# LoRa_stm32.net
KiCad netlist of a schematic drawn in Altium Designer
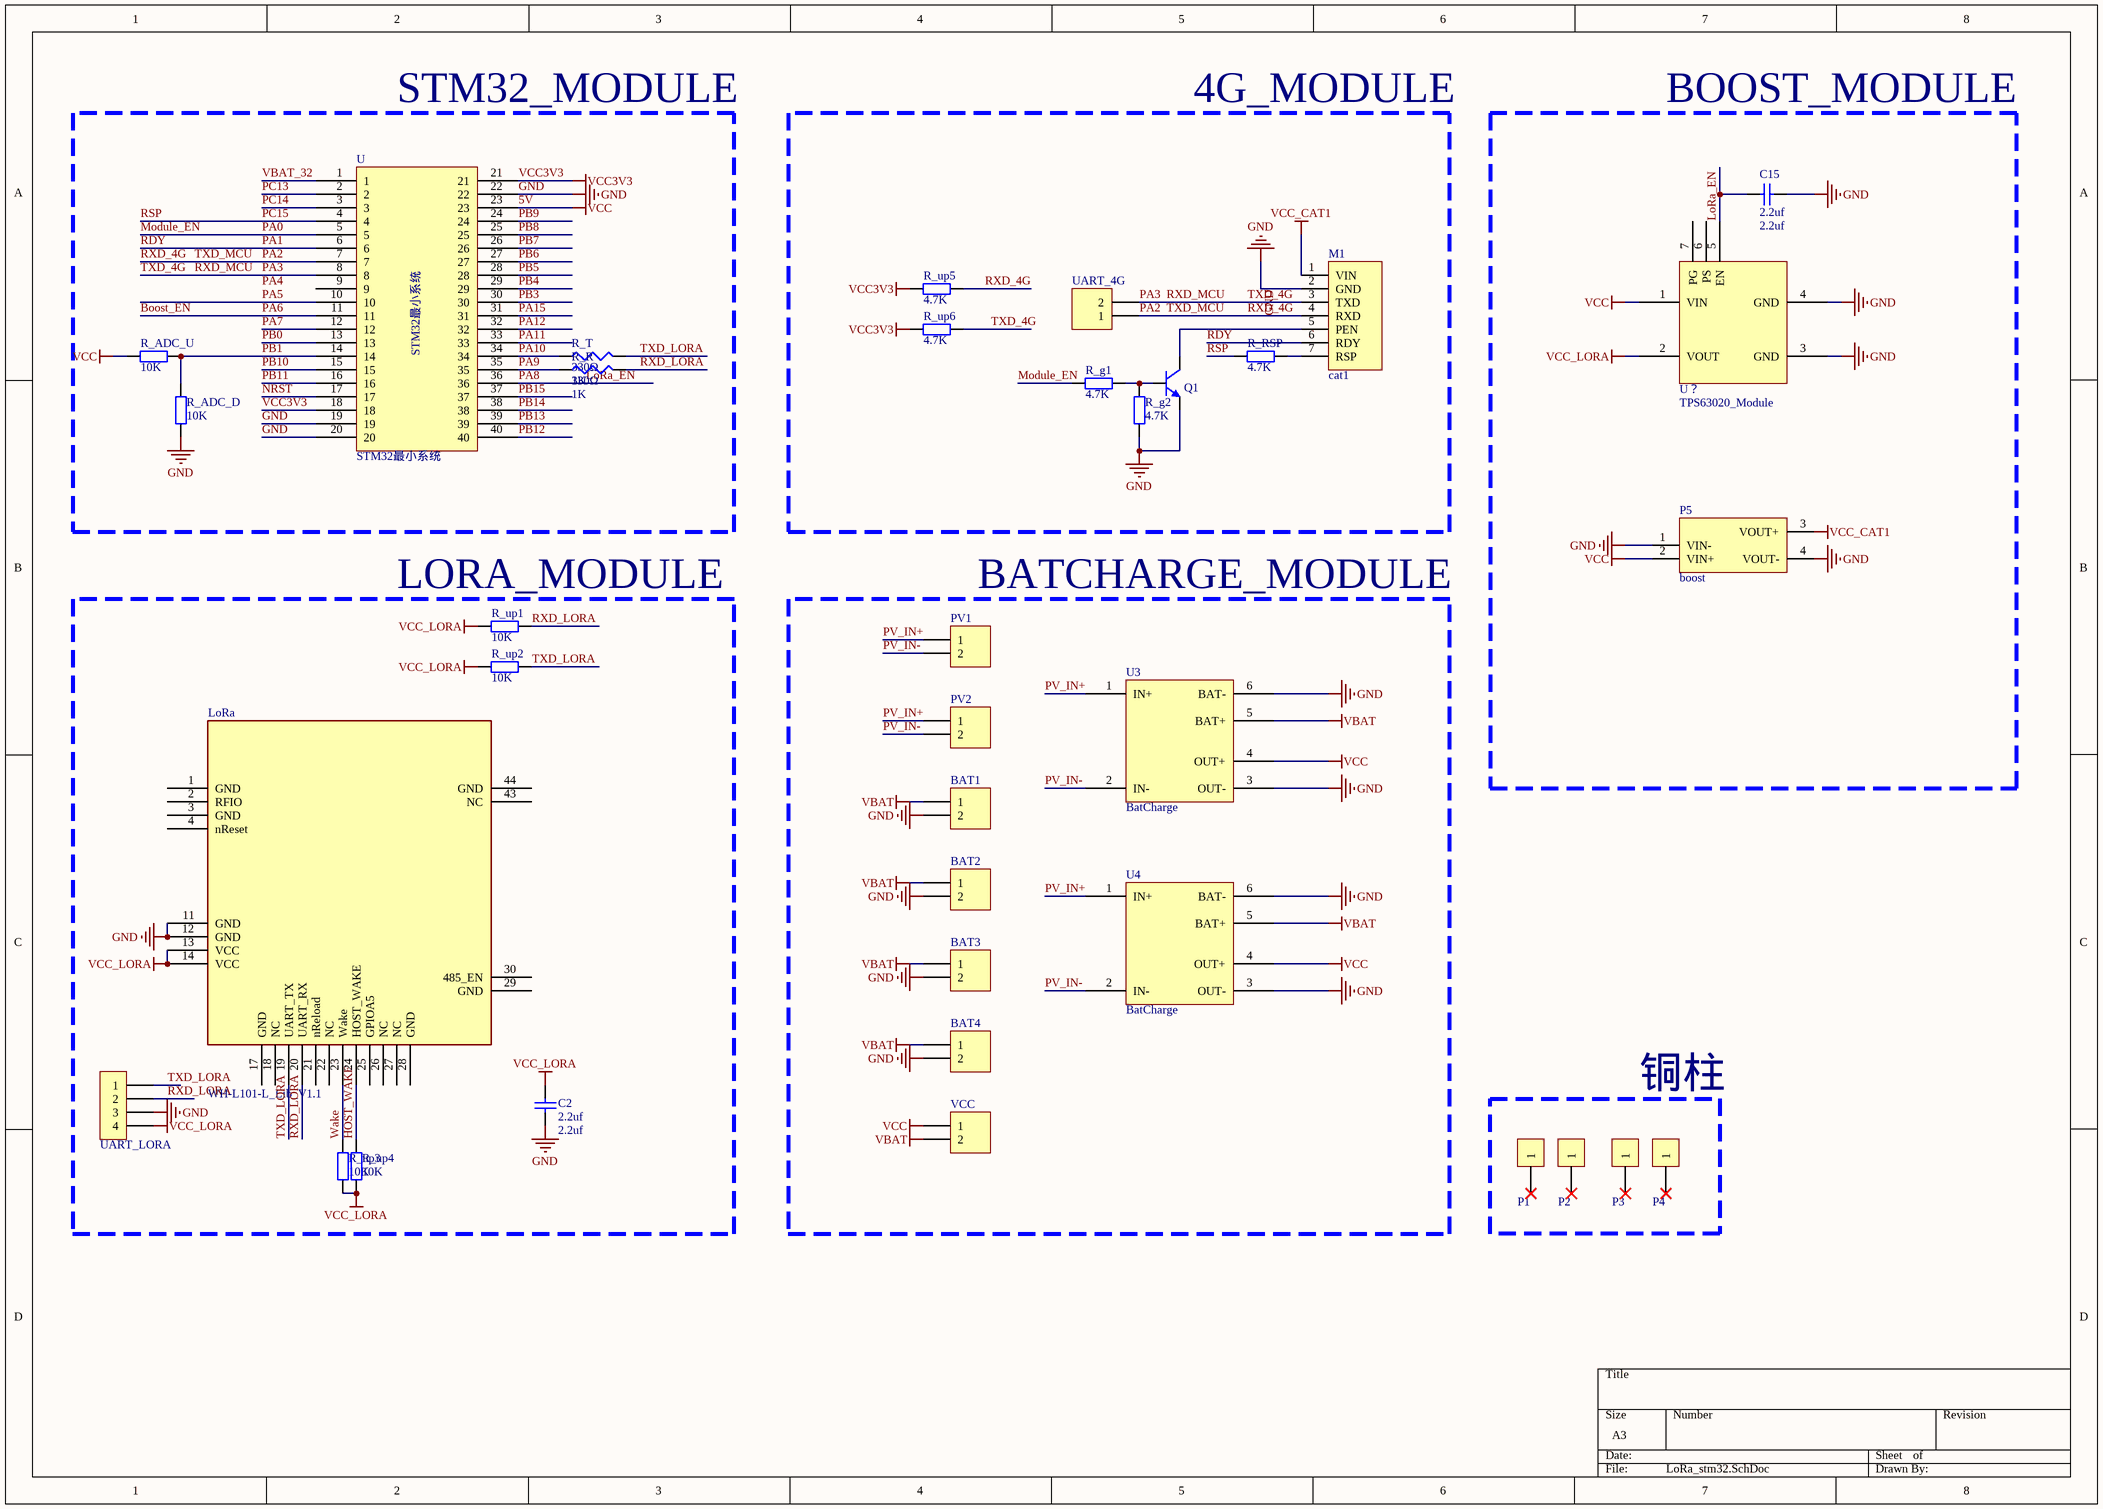
[diagram p0: LoRa_stm32.SchDoc]

(export (version "E")
  (design (tool "Eeschema 10.0.6"))
  (components
    (comp (ref "BAT1")
      (value "UART_4G")
      (footprint "XH-2P")
      (description "Header, 2-Pin")
      (fields (field (name "PUBLISHER") "Altium Limited"))
      (libsource (lib "Miscellaneous Connectors") (part "Header 2"))
    )
    (comp (ref "BAT2")
      (value "UART_4G")
      (footprint "XH-2P")
      (description "Header, 2-Pin")
      (fields (field (name "PUBLISHER") "Altium Limited"))
      (libsource (lib "Miscellaneous Connectors") (part "Header 2"))
    )
    (comp (ref "BAT3")
      (value "UART_4G")
      (footprint "XH-2P")
      (description "Header, 2-Pin")
      (fields (field (name "PUBLISHER") "Altium Limited"))
      (libsource (lib "Miscellaneous Connectors") (part "Header 2"))
    )
    (comp (ref "BAT4")
      (value "UART_4G")
      (footprint "XH-2P")
      (description "Header, 2-Pin")
      (fields (field (name "PUBLISHER") "Altium Limited"))
      (libsource (lib "Miscellaneous Connectors") (part "Header 2"))
    )
    (comp (ref "C2")
      (value "2.2uf")
      (footprint "Csust_czq6:0603-C")
      (description "Capacitor")
      (fields (field (name "ALTIUM_VALUE") "2.2uf") (field (name "PUBLISHER") "Altium Limited"))
      (libsource (lib "PCB_Project") (part "Cap"))
    )
    (comp (ref "C15")
      (value "2.2uf")
      (footprint "Csust_czq6:0603-C")
      (description "Capacitor")
      (fields (field (name "ALTIUM_VALUE") "2.2uf") (field (name "PUBLISHER") "Altium Limited"))
      (libsource (lib "PCB_Project") (part "Cap"))
    )
    (comp (ref "LoRa")
      (value "WH-L101-L_Lib_V1.1")
      (footprint "SMD-44_18.22X26.65X1.27P")
      (libsource (lib "steven") (part "WH-L101-L_Lib_V1.1"))
    )
    (comp (ref "M1")
      (value "cat1")
      (footprint "MCore724")
      (description "4G透传模块")
      (libsource (lib "steven") (part "MCore_A724UG"))
    )
    (comp (ref "P1") (value "铜柱孔") (footprint "铜柱孔") (libsource (lib "Csust_czq6") (part "铜柱孔")))
    (comp (ref "P2") (value "铜柱孔") (footprint "铜柱孔") (libsource (lib "Csust_czq6") (part "铜柱孔")))
    (comp (ref "P3") (value "铜柱孔") (footprint "铜柱孔") (libsource (lib "Csust_czq6") (part "铜柱孔")))
    (comp (ref "P4") (value "铜柱孔") (footprint "铜柱孔") (libsource (lib "Csust_czq6") (part "铜柱孔")))
    (comp (ref "P5")
      (value "boost")
      (footprint "锂电池升压")
      (description "锂电池升压至5/8/9/12V")
      (libsource (lib "steven") (part "Boost12V"))
    )
    (comp (ref "PV1")
      (value "UART_4G")
      (footprint "XH-2P")
      (description "Header, 2-Pin")
      (fields (field (name "PUBLISHER") "Altium Limited"))
      (libsource (lib "Miscellaneous Connectors") (part "Header 2"))
    )
    (comp (ref "PV2")
      (value "UART_4G")
      (footprint "XH-2P")
      (description "Header, 2-Pin")
      (fields (field (name "PUBLISHER") "Altium Limited"))
      (libsource (lib "Miscellaneous Connectors") (part "Header 2"))
    )
    (comp (ref "Q1") (value "三极管(NPN)") (footprint "TO-92") (libsource (lib "Csust_czq6") (part "三极管(NPN)")))
    (comp (ref "R_ADC_D")
      (value "10K")
      (footprint "Csust_czq6:0603-R")
      (description "贴片电阻")
      (fields (field (name "PUBLISHER") "Altium Limited"))
      (libsource (lib "") (part "Res1_1"))
    )
    (comp (ref "R_ADC_U")
      (value "10K")
      (footprint "Csust_czq6:0603-R")
      (description "贴片电阻")
      (fields (field (name "PUBLISHER") "Altium Limited"))
      (libsource (lib "Fszhang") (part "Res1"))
    )
    (comp (ref "R_g1")
      (value "4.7K")
      (footprint "Csust_czq6:0603-R")
      (description "贴片电阻")
      (fields (field (name "Comment") "10K") (field (name "PUBLISHER") "Altium Limited"))
      (libsource (lib "Fszhang") (part "Res1"))
    )
    (comp (ref "R_g2")
      (value "4.7K")
      (footprint "Csust_czq6:0603-R")
      (description "贴片电阻")
      (fields (field (name "Comment") "10K") (field (name "PUBLISHER") "Altium Limited"))
      (libsource (lib "") (part "Res1_1"))
    )
    (comp (ref "R_R")
      (value "330Ω")
      (footprint "J1-0603")
      (description "Resistor")
      (fields (field (name "ALTIUM_VALUE") "1K") (field (name "PUBLISHER") "Altium Limited"))
      (libsource (lib "Miscellaneous Devices") (part "Res3"))
    )
    (comp (ref "R_RSP")
      (value "4.7K")
      (footprint "Csust_czq6:0603-R")
      (description "贴片电阻")
      (fields (field (name "Comment") "10K") (field (name "PUBLISHER") "Altium Limited"))
      (libsource (lib "Fszhang") (part "Res1"))
    )
    (comp (ref "R_T")
      (value "330Ω")
      (footprint "J1-0603")
      (description "Resistor")
      (fields (field (name "ALTIUM_VALUE") "1K") (field (name "PUBLISHER") "Altium Limited"))
      (libsource (lib "Miscellaneous Devices") (part "Res3"))
    )
    (comp (ref "R_up1")
      (value "10K")
      (footprint "Csust_czq6:0603-R")
      (description "贴片电阻")
      (fields (field (name "PUBLISHER") "Altium Limited"))
      (libsource (lib "Fszhang") (part "Res1"))
    )
    (comp (ref "R_up2")
      (value "10K")
      (footprint "Csust_czq6:0603-R")
      (description "贴片电阻")
      (fields (field (name "PUBLISHER") "Altium Limited"))
      (libsource (lib "Fszhang") (part "Res1"))
    )
    (comp (ref "R_up3")
      (value "10K")
      (footprint "Csust_czq6:0603-R")
      (description "贴片电阻")
      (fields (field (name "PUBLISHER") "Altium Limited"))
      (libsource (lib "") (part "Res1_1"))
    )
    (comp (ref "R_up4")
      (value "10K")
      (footprint "Csust_czq6:0603-R")
      (description "贴片电阻")
      (fields (field (name "PUBLISHER") "Altium Limited"))
      (libsource (lib "") (part "Res1_1"))
    )
    (comp (ref "R_up5")
      (value "4.7K")
      (footprint "Csust_czq6:0603-R")
      (description "贴片电阻")
      (fields (field (name "Comment") "10K") (field (name "PUBLISHER") "Altium Limited"))
      (libsource (lib "Fszhang") (part "Res1"))
    )
    (comp (ref "R_up6")
      (value "4.7K")
      (footprint "Csust_czq6:0603-R")
      (description "贴片电阻")
      (fields (field (name "Comment") "10K") (field (name "PUBLISHER") "Altium Limited"))
      (libsource (lib "Fszhang") (part "Res1"))
    )
    (comp (ref "U") (value "STM32最小系统") (footprint "STM32最小系统") (libsource (lib "steven") (part "STM32最小系统")))
    (comp (ref "U3")
      (value "BatCharge")
      (footprint "Bat_Charge")
      (description "电池充电模块")
      (libsource (lib "steven") (part "BatCharge"))
    )
    (comp (ref "U4")
      (value "BatCharge")
      (footprint "Bat_Charge")
      (description "电池充电模块")
      (libsource (lib "steven") (part "BatCharge"))
    )
    (comp (ref "UART_4G")
      (value "UART_4G")
      (footprint "HDR1X2")
      (description "Header, 2-Pin")
      (fields (field (name "PUBLISHER") "Altium Limited"))
      (libsource (lib "") (part "Header 2_1"))
    )
    (comp (ref "UART_LORA")
      (value "XH接线座-4P")
      (footprint "HDR1X4")
      (libsource (lib "Csust_czq6") (part "XH接线座-4P"))
    )
    (comp (ref "U？")
      (value "TPS63020_Module")
      (footprint "TP63020_MODULE")
      (description "升压模块模块")
      (libsource (lib "steven") (part "TPS63020_Module"))
    )
    (comp (ref "VCC")
      (value "UART_4G")
      (footprint "Header1X2")
      (description "Header, 2-Pin")
      (fields (field (name "PUBLISHER") "Altium Limited"))
      (libsource (lib "Miscellaneous Connectors") (part "Header 2"))
    )
  )
  (nets
    (net (code "1") (name "/Boost_EN") (class "Default")
      (node (ref "U") (pin "11") (pinfunction "11_11") (pintype "passive"))
    )
    (net (code "2") (name "/HOST_WAKE") (class "Default")
      (node (ref "LoRa") (pin "24") (pinfunction "HOST_WAKE_24") (pintype "passive"))
      (node (ref "R_up4") (pin "1") (pinfunction "1_1") (pintype "passive"))
    )
    (net (code "3") (name "/LoRa_EN") (class "Default")
      (node (ref "C15") (pin "1") (pinfunction "1_1") (pintype "passive"))
      (node (ref "U") (pin "36") (pinfunction "36_36") (pintype "passive"))
      (node (ref "U？") (pin "5") (pinfunction "EN_5") (pintype "passive"))
    )
    (net (code "4") (name "/Module_EN") (class "Default")
      (node (ref "R_g1") (pin "2") (pinfunction "2_2") (pintype "passive"))
      (node (ref "U") (pin "5") (pinfunction "5_5") (pintype "passive"))
    )
    (net (code "5") (name "/NRST") (class "Default")
      (node (ref "U") (pin "17") (pinfunction "17_17") (pintype "passive"))
    )
    (net (code "6") (name "/PA1") (class "Default")
      (node (ref "M1") (pin "6") (pinfunction "RDY_6") (pintype "passive"))
      (node (ref "U") (pin "6") (pinfunction "6_6") (pintype "passive"))
    )
    (net (code "7") (name "/PA2") (class "Default")
      (node (ref "M1") (pin "4") (pinfunction "RXD_4") (pintype "passive"))
      (node (ref "R_up5") (pin "1") (pinfunction "1_1") (pintype "passive"))
      (node (ref "U") (pin "7") (pinfunction "7_7") (pintype "passive"))
      (node (ref "UART_4G") (pin "1") (pinfunction "1_1") (pintype "passive"))
    )
    (net (code "8") (name "/PA3") (class "Default")
      (node (ref "M1") (pin "3") (pinfunction "TXD_3") (pintype "passive"))
      (node (ref "R_up6") (pin "1") (pinfunction "1_1") (pintype "passive"))
      (node (ref "U") (pin "8") (pinfunction "8_8") (pintype "passive"))
      (node (ref "UART_4G") (pin "2") (pinfunction "2_2") (pintype "passive"))
    )
    (net (code "10") (name "/PA5") (class "Default")
      (node (ref "U") (pin "10") (pinfunction "10_10") (pintype "passive"))
    )
    (net (code "11") (name "/PA7") (class "Default")
      (node (ref "U") (pin "12") (pinfunction "12_12") (pintype "passive"))
    )
    (net (code "12") (name "/PA9") (class "Default")
      (node (ref "R_R") (pin "1") (pinfunction "1_1") (pintype "passive"))
      (node (ref "U") (pin "35") (pinfunction "35_35") (pintype "passive"))
    )
    (net (code "13") (name "/PA10") (class "Default")
      (node (ref "R_T") (pin "1") (pinfunction "1_1") (pintype "passive"))
      (node (ref "U") (pin "34") (pinfunction "34_34") (pintype "passive"))
    )
    (net (code "14") (name "/PA11") (class "Default")
      (node (ref "U") (pin "33") (pinfunction "33_33") (pintype "passive"))
    )
    (net (code "15") (name "/PA12") (class "Default")
      (node (ref "U") (pin "32") (pinfunction "32_32") (pintype "passive"))
    )
    (net (code "16") (name "/PA15") (class "Default")
      (node (ref "U") (pin "31") (pinfunction "31_31") (pintype "passive"))
    )
    (net (code "17") (name "/PB0") (class "Default")
      (node (ref "U") (pin "13") (pinfunction "13_13") (pintype "passive"))
    )
    (net (code "18") (name "/PB1") (class "Default")
      (node (ref "R_ADC_D") (pin "1") (pinfunction "1_1") (pintype "passive"))
      (node (ref "R_ADC_U") (pin "1") (pinfunction "1_1") (pintype "passive"))
      (node (ref "U") (pin "14") (pinfunction "14_14") (pintype "passive"))
    )
    (net (code "19") (name "/PB3") (class "Default")
      (node (ref "U") (pin "30") (pinfunction "30_30") (pintype "passive"))
    )
    (net (code "20") (name "/PB4") (class "Default")
      (node (ref "U") (pin "29") (pinfunction "29_29") (pintype "passive"))
    )
    (net (code "21") (name "/PB5") (class "Default")
      (node (ref "U") (pin "28") (pinfunction "28_28") (pintype "passive"))
    )
    (net (code "22") (name "/PB6") (class "Default")
      (node (ref "U") (pin "27") (pinfunction "27_27") (pintype "passive"))
    )
    (net (code "23") (name "/PB7") (class "Default")
      (node (ref "U") (pin "26") (pinfunction "26_26") (pintype "passive"))
    )
    (net (code "24") (name "/PB8") (class "Default")
      (node (ref "U") (pin "25") (pinfunction "25_25") (pintype "passive"))
    )
    (net (code "25") (name "/PB9") (class "Default")
      (node (ref "U") (pin "24") (pinfunction "24_24") (pintype "passive"))
    )
    (net (code "26") (name "/PB10") (class "Default")
      (node (ref "U") (pin "15") (pinfunction "15_15") (pintype "passive"))
    )
    (net (code "27") (name "/PB11") (class "Default")
      (node (ref "U") (pin "16") (pinfunction "16_16") (pintype "passive"))
    )
    (net (code "28") (name "/PB12") (class "Default")
      (node (ref "U") (pin "40") (pinfunction "40_40") (pintype "passive"))
    )
    (net (code "29") (name "/PB13") (class "Default")
      (node (ref "U") (pin "39") (pinfunction "39_39") (pintype "passive"))
    )
    (net (code "30") (name "/PB14") (class "Default")
      (node (ref "U") (pin "38") (pinfunction "38_38") (pintype "passive"))
    )
    (net (code "31") (name "/PB15") (class "Default")
      (node (ref "U") (pin "37") (pinfunction "37_37") (pintype "passive"))
    )
    (net (code "32") (name "/PC13") (class "Default")
      (node (ref "U") (pin "2") (pinfunction "2_2") (pintype "passive"))
    )
    (net (code "33") (name "/PC14") (class "Default")
      (node (ref "U") (pin "3") (pinfunction "3_3") (pintype "passive"))
    )
    (net (code "34") (name "/PC15") (class "Default")
      (node (ref "R_RSP") (pin "2") (pinfunction "2_2") (pintype "passive"))
      (node (ref "U") (pin "4") (pinfunction "4_4") (pintype "passive"))
    )
    (net (code "35") (name "/PV_IN+") (class "Default")
      (node (ref "PV1") (pin "1") (pinfunction "1_1") (pintype "passive"))
      (node (ref "PV2") (pin "1") (pinfunction "1_1") (pintype "passive"))
      (node (ref "U3") (pin "1") (pinfunction "IN+_1") (pintype "passive"))
      (node (ref "U4") (pin "1") (pinfunction "IN+_1") (pintype "passive"))
    )
    (net (code "36") (name "/PV_IN-") (class "Default")
      (node (ref "PV1") (pin "2") (pinfunction "2_2") (pintype "passive"))
      (node (ref "PV2") (pin "2") (pinfunction "2_2") (pintype "passive"))
      (node (ref "U3") (pin "2") (pinfunction "IN-_2") (pintype "passive"))
      (node (ref "U4") (pin "2") (pinfunction "IN-_2") (pintype "passive"))
    )
    (net (code "37") (name "/RXD_LORA") (class "Default")
      (node (ref "LoRa") (pin "20") (pinfunction "UART_RX_20") (pintype "passive"))
      (node (ref "R_R") (pin "2") (pinfunction "2_2") (pintype "passive"))
      (node (ref "R_up1") (pin "1") (pinfunction "1_1") (pintype "passive"))
      (node (ref "UART_LORA") (pin "2") (pinfunction "2_2") (pintype "passive"))
    )
    (net (code "38") (name "/TXD_LORA") (class "Default")
      (node (ref "LoRa") (pin "19") (pinfunction "UART_TX_19") (pintype "passive"))
      (node (ref "R_T") (pin "2") (pinfunction "2_2") (pintype "passive"))
      (node (ref "R_up2") (pin "1") (pinfunction "1_1") (pintype "passive"))
      (node (ref "UART_LORA") (pin "1") (pinfunction "1_1") (pintype "passive"))
    )
    (net (code "39") (name "/VBAT_32") (class "Default")
      (node (ref "U") (pin "1") (pinfunction "1_1") (pintype "passive"))
    )
    (net (code "40") (name "/Wake") (class "Default")
      (node (ref "LoRa") (pin "23") (pinfunction "Wake_23") (pintype "passive"))
      (node (ref "R_up3") (pin "1") (pinfunction "1_1") (pintype "passive"))
    )
    (net (code "41") (name "GND") (class "Default")
      (node (ref "BAT1") (pin "2") (pinfunction "2_2") (pintype "passive"))
      (node (ref "BAT2") (pin "2") (pinfunction "2_2") (pintype "passive"))
      (node (ref "BAT3") (pin "2") (pinfunction "2_2") (pintype "passive"))
      (node (ref "BAT4") (pin "2") (pinfunction "2_2") (pintype "passive"))
      (node (ref "C15") (pin "2") (pinfunction "2_2") (pintype "passive"))
      (node (ref "C2") (pin "2") (pinfunction "2_2") (pintype "passive"))
      (node (ref "LoRa") (pin "11") (pinfunction "GND_11") (pintype "passive"))
      (node (ref "LoRa") (pin "12") (pinfunction "GND_12") (pintype "passive"))
      (node (ref "M1") (pin "2") (pinfunction "GND_2") (pintype "passive"))
      (node (ref "P5") (pin "1") (pinfunction "VIN-_1") (pintype "passive"))
      (node (ref "P5") (pin "4") (pinfunction "VOUT-_4") (pintype "passive"))
      (node (ref "Q1") (pin "1") (pinfunction "E_1") (pintype "passive"))
      (node (ref "R_ADC_D") (pin "2") (pinfunction "2_2") (pintype "passive"))
      (node (ref "R_g2") (pin "2") (pinfunction "2_2") (pintype "passive"))
      (node (ref "U") (pin "19") (pinfunction "19_19") (pintype "passive"))
      (node (ref "U") (pin "20") (pinfunction "20_20") (pintype "passive"))
      (node (ref "U") (pin "22") (pinfunction "22_22") (pintype "passive"))
      (node (ref "U3") (pin "3") (pinfunction "OUT-_3") (pintype "passive"))
      (node (ref "U3") (pin "6") (pinfunction "BAT-_6") (pintype "passive"))
      (node (ref "U4") (pin "3") (pinfunction "OUT-_3") (pintype "passive"))
      (node (ref "U4") (pin "6") (pinfunction "BAT-_6") (pintype "passive"))
      (node (ref "UART_LORA") (pin "3") (pinfunction "3_3") (pintype "passive"))
      (node (ref "U？") (pin "3") (pinfunction "GND_3") (pintype "passive"))
      (node (ref "U？") (pin "4") (pinfunction "GND_4") (pintype "passive"))
    )
    (net (code "42") (name "Net-(M1-PEN)") (class "Default")
      (node (ref "M1") (pin "5") (pinfunction "PEN_5") (pintype "passive"))
      (node (ref "Q1") (pin "3") (pinfunction "C_3") (pintype "passive"))
    )
    (net (code "43") (name "Net-(M1-RSP)") (class "Default")
      (node (ref "M1") (pin "7") (pinfunction "RSP_7") (pintype "passive"))
      (node (ref "R_RSP") (pin "1") (pinfunction "1_1") (pintype "passive"))
    )
    (net (code "44") (name "Net-(Q1-B)") (class "Default")
      (node (ref "Q1") (pin "2") (pinfunction "B_2") (pintype "passive"))
      (node (ref "R_g1") (pin "1") (pinfunction "1_1") (pintype "passive"))
      (node (ref "R_g2") (pin "1") (pinfunction "1_1") (pintype "passive"))
    )
    (net (code "45") (name "VBAT") (class "Default")
      (node (ref "BAT1") (pin "1") (pinfunction "1_1") (pintype "passive"))
      (node (ref "BAT2") (pin "1") (pinfunction "1_1") (pintype "passive"))
      (node (ref "BAT3") (pin "1") (pinfunction "1_1") (pintype "passive"))
      (node (ref "BAT4") (pin "1") (pinfunction "1_1") (pintype "passive"))
      (node (ref "U3") (pin "5") (pinfunction "BAT+_5") (pintype "passive"))
      (node (ref "U4") (pin "5") (pinfunction "BAT+_5") (pintype "passive"))
      (node (ref "VCC") (pin "2") (pinfunction "2_2") (pintype "passive"))
    )
    (net (code "46") (name "VCC") (class "Default")
      (node (ref "P5") (pin "2") (pinfunction "VIN+_2") (pintype "passive"))
      (node (ref "R_ADC_U") (pin "2") (pinfunction "2_2") (pintype "passive"))
      (node (ref "U") (pin "23") (pinfunction "23_23") (pintype "passive"))
      (node (ref "U3") (pin "4") (pinfunction "OUT+_4") (pintype "passive"))
      (node (ref "U4") (pin "4") (pinfunction "OUT+_4") (pintype "passive"))
      (node (ref "U？") (pin "1") (pinfunction "VIN_1") (pintype "passive"))
      (node (ref "VCC") (pin "1") (pinfunction "1_1") (pintype "passive"))
    )
    (net (code "47") (name "VCC3V3") (class "Default")
      (node (ref "R_up5") (pin "2") (pinfunction "2_2") (pintype "passive"))
      (node (ref "R_up6") (pin "2") (pinfunction "2_2") (pintype "passive"))
      (node (ref "U") (pin "18") (pinfunction "18_18") (pintype "passive"))
      (node (ref "U") (pin "21") (pinfunction "21_21") (pintype "passive"))
    )
    (net (code "48") (name "VCC_CAT1") (class "Default")
      (node (ref "M1") (pin "1") (pinfunction "VIN_1") (pintype "passive"))
      (node (ref "P5") (pin "3") (pinfunction "VOUT+_3") (pintype "passive"))
    )
    (net (code "49") (name "VCC_LORA") (class "Default")
      (node (ref "C2") (pin "1") (pinfunction "1_1") (pintype "passive"))
      (node (ref "LoRa") (pin "13") (pinfunction "VCC_13") (pintype "passive"))
      (node (ref "LoRa") (pin "14") (pinfunction "VCC_14") (pintype "passive"))
      (node (ref "R_up1") (pin "2") (pinfunction "2_2") (pintype "passive"))
      (node (ref "R_up2") (pin "2") (pinfunction "2_2") (pintype "passive"))
      (node (ref "R_up3") (pin "2") (pinfunction "2_2") (pintype "passive"))
      (node (ref "R_up4") (pin "2") (pinfunction "2_2") (pintype "passive"))
      (node (ref "UART_LORA") (pin "4") (pinfunction "4_4") (pintype "passive"))
      (node (ref "U？") (pin "2") (pinfunction "VOUT_2") (pintype "passive"))
    )
    (net (code "50") (name "unconnected-(LoRa-485_EN-Pad30)") (class "Default")
      (node (ref "LoRa") (pin "30") (pinfunction "485_EN_30") (pintype "passive"))
    )
    (net (code "51") (name "unconnected-(LoRa-GND-Pad1)") (class "Default")
      (node (ref "LoRa") (pin "1") (pinfunction "GND_1") (pintype "passive"))
    )
    (net (code "52") (name "unconnected-(LoRa-GND-Pad3)") (class "Default")
      (node (ref "LoRa") (pin "3") (pinfunction "GND_3") (pintype "passive"))
    )
    (net (code "53") (name "unconnected-(LoRa-GND-Pad17)") (class "Default")
      (node (ref "LoRa") (pin "17") (pinfunction "GND_17") (pintype "passive"))
    )
    (net (code "54") (name "unconnected-(LoRa-GND-Pad28)") (class "Default")
      (node (ref "LoRa") (pin "28") (pinfunction "GND_28") (pintype "passive"))
    )
    (net (code "55") (name "unconnected-(LoRa-GND-Pad29)") (class "Default")
      (node (ref "LoRa") (pin "29") (pinfunction "GND_29") (pintype "passive"))
    )
    (net (code "56") (name "unconnected-(LoRa-GND-Pad44)") (class "Default")
      (node (ref "LoRa") (pin "44") (pinfunction "GND_44") (pintype "passive"))
    )
    (net (code "57") (name "unconnected-(LoRa-GPIOA5-Pad25)") (class "Default")
      (node (ref "LoRa") (pin "25") (pinfunction "GPIOA5_25") (pintype "passive"))
    )
    (net (code "58") (name "unconnected-(LoRa-NC-Pad18)") (class "Default")
      (node (ref "LoRa") (pin "18") (pinfunction "NC_18") (pintype "passive"))
    )
    (net (code "59") (name "unconnected-(LoRa-NC-Pad22)") (class "Default")
      (node (ref "LoRa") (pin "22") (pinfunction "NC_22") (pintype "passive"))
    )
    (net (code "60") (name "unconnected-(LoRa-NC-Pad26)") (class "Default")
      (node (ref "LoRa") (pin "26") (pinfunction "NC_26") (pintype "passive"))
    )
    (net (code "61") (name "unconnected-(LoRa-NC-Pad27)") (class "Default")
      (node (ref "LoRa") (pin "27") (pinfunction "NC_27") (pintype "passive"))
    )
    (net (code "62") (name "unconnected-(LoRa-NC-Pad43)") (class "Default")
      (node (ref "LoRa") (pin "43") (pinfunction "NC_43") (pintype "passive"))
    )
    (net (code "63") (name "unconnected-(LoRa-RFIO-Pad2)") (class "Default")
      (node (ref "LoRa") (pin "2") (pinfunction "RFIO_2") (pintype "passive"))
    )
    (net (code "64") (name "unconnected-(LoRa-nReload-Pad21)") (class "Default")
      (node (ref "LoRa") (pin "21") (pinfunction "nReload_21") (pintype "passive"))
    )
    (net (code "65") (name "unconnected-(LoRa-nReset-Pad4)") (class "Default")
      (node (ref "LoRa") (pin "4") (pinfunction "nReset_4") (pintype "passive"))
    )
    (net (code "66") (name "unconnected-(P1-Pad1)") (class "Default")
      (node (ref "P1") (pin "1") (pinfunction "1_1") (pintype "passive+no_connect"))
    )
    (net (code "67") (name "unconnected-(P2-Pad1)") (class "Default")
      (node (ref "P2") (pin "1") (pinfunction "1_1") (pintype "passive+no_connect"))
    )
    (net (code "68") (name "unconnected-(P3-Pad1)") (class "Default")
      (node (ref "P3") (pin "1") (pinfunction "1_1") (pintype "passive+no_connect"))
    )
    (net (code "69") (name "unconnected-(P4-Pad1)") (class "Default")
      (node (ref "P4") (pin "1") (pinfunction "1_1") (pintype "passive+no_connect"))
    )
    (net (code "70") (name "unconnected-(U-Pad9)") (class "Default")
      (node (ref "U") (pin "9") (pinfunction "9_9") (pintype "passive"))
    )
    (net (code "71") (name "unconnected-(U？-PG-Pad7)") (class "Default")
      (node (ref "U？") (pin "7") (pinfunction "PG_7") (pintype "passive"))
    )
    (net (code "72") (name "unconnected-(U？-PS-Pad6)") (class "Default")
      (node (ref "U？") (pin "6") (pinfunction "PS_6") (pintype "passive"))
    )
  )
)
